# PARAMETRIK_crosover.net
KiCad netlist of a schematic drawn in EAGLE
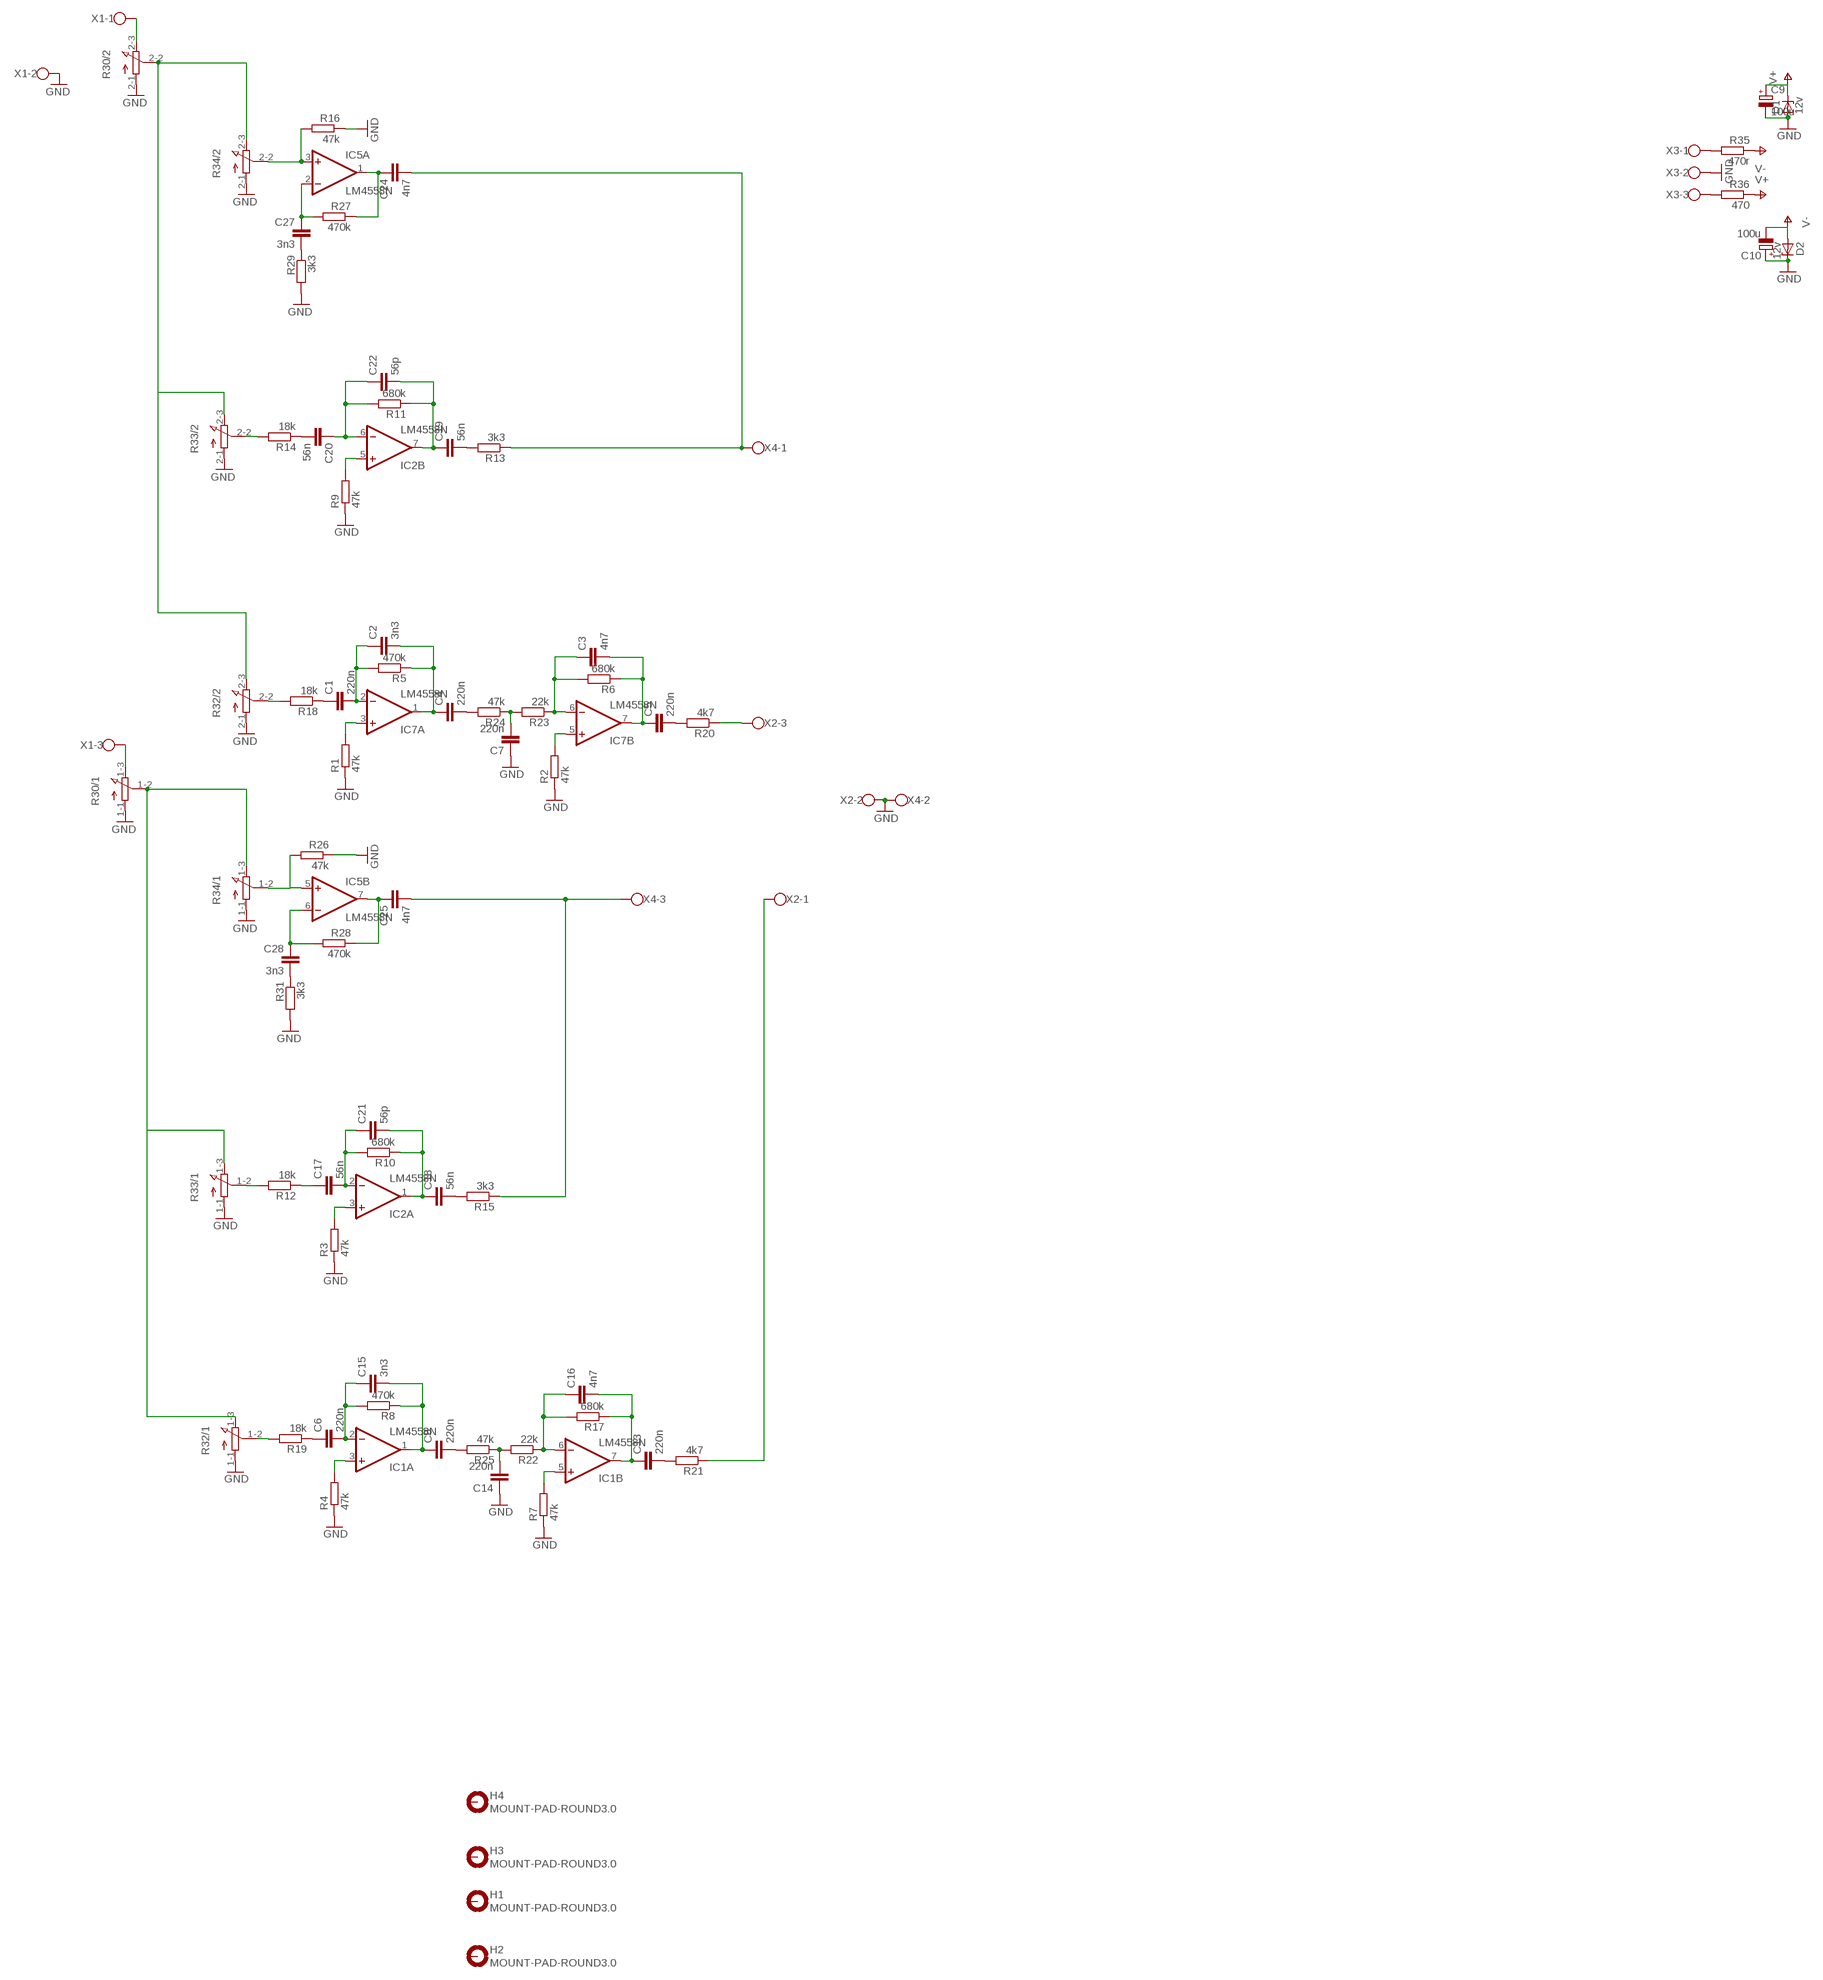
[diagram p0: schematic, sheet 1]

(export (version "E")
  (design (tool "Eeschema 10.0.6"))
  (components
    (comp (ref "C1")
      (value "220n")
      (footprint "eagle-import:C075-032X103")
      (libsource (lib "eagle-import") (part "C-EU075-032X103"))
    )
    (comp (ref "C2")
      (value "3n3")
      (footprint "eagle-import:C025-025X050")
      (libsource (lib "eagle-import") (part "C-EU025-025X050"))
    )
    (comp (ref "C3")
      (value "4n7")
      (footprint "eagle-import:C025-025X050")
      (libsource (lib "eagle-import") (part "C-EU025-025X050"))
    )
    (comp (ref "C4")
      (value "220n")
      (footprint "eagle-import:C075-032X103")
      (libsource (lib "eagle-import") (part "C-EU075-032X103"))
    )
    (comp (ref "C5")
      (value "220n")
      (footprint "eagle-import:C075-032X103")
      (libsource (lib "eagle-import") (part "C-EU075-032X103"))
    )
    (comp (ref "C6")
      (value "220n")
      (footprint "eagle-import:C075-032X103")
      (libsource (lib "eagle-import") (part "C-EU075-032X103"))
    )
    (comp (ref "C7")
      (value "220n")
      (footprint "eagle-import:C075-032X103")
      (libsource (lib "eagle-import") (part "C-EU075-032X103"))
    )
    (comp (ref "C8")
      (value "220n")
      (footprint "eagle-import:C075-032X103")
      (libsource (lib "eagle-import") (part "C-EU075-032X103"))
    )
    (comp (ref "C9")
      (value "100u")
      (footprint "eagle-import:E2,5-6")
      (libsource (lib "eagle-import") (part "CPOL-EUE2.5-6"))
    )
    (comp (ref "C10")
      (value "100u")
      (footprint "eagle-import:E2,5-6")
      (libsource (lib "eagle-import") (part "CPOL-EUE2.5-6"))
    )
    (comp (ref "C13")
      (value "220n")
      (footprint "eagle-import:C075-032X103")
      (libsource (lib "eagle-import") (part "C-EU075-032X103"))
    )
    (comp (ref "C14")
      (value "220n")
      (footprint "eagle-import:C075-032X103")
      (libsource (lib "eagle-import") (part "C-EU075-032X103"))
    )
    (comp (ref "C15")
      (value "3n3")
      (footprint "eagle-import:C025-025X050")
      (libsource (lib "eagle-import") (part "C-EU025-025X050"))
    )
    (comp (ref "C16")
      (value "4n7")
      (footprint "eagle-import:C025-025X050")
      (libsource (lib "eagle-import") (part "C-EU025-025X050"))
    )
    (comp (ref "C17")
      (value "56n")
      (footprint "eagle-import:C075-032X103")
      (libsource (lib "eagle-import") (part "C-EU075-032X103"))
    )
    (comp (ref "C18")
      (value "56n")
      (footprint "eagle-import:C075-032X103")
      (libsource (lib "eagle-import") (part "C-EU075-032X103"))
    )
    (comp (ref "C19")
      (value "56n")
      (footprint "eagle-import:C075-032X103")
      (libsource (lib "eagle-import") (part "C-EU075-032X103"))
    )
    (comp (ref "C20")
      (value "56n")
      (footprint "eagle-import:C075-032X103")
      (libsource (lib "eagle-import") (part "C-EU075-032X103"))
    )
    (comp (ref "C21")
      (value "56p")
      (footprint "eagle-import:C025-025X050")
      (libsource (lib "eagle-import") (part "C-EU025-025X050"))
    )
    (comp (ref "C22")
      (value "56p")
      (footprint "eagle-import:C025-025X050")
      (libsource (lib "eagle-import") (part "C-EU025-025X050"))
    )
    (comp (ref "C24")
      (value "4n7")
      (footprint "eagle-import:C075-032X103")
      (libsource (lib "eagle-import") (part "C-EU075-032X103"))
    )
    (comp (ref "C25")
      (value "4n7")
      (footprint "eagle-import:C075-032X103")
      (libsource (lib "eagle-import") (part "C-EU075-032X103"))
    )
    (comp (ref "C27")
      (value "3n3")
      (footprint "eagle-import:C025-025X050")
      (libsource (lib "eagle-import") (part "C-EU025-025X050"))
    )
    (comp (ref "C28")
      (value "3n3")
      (footprint "eagle-import:C025-025X050")
      (libsource (lib "eagle-import") (part "C-EU025-025X050"))
    )
    (comp (ref "D1")
      (value "12v")
      (footprint "eagle-import:DO35Z10")
      (libsource (lib "eagle-import") (part "1N821"))
    )
    (comp (ref "D2")
      (value "12v")
      (footprint "eagle-import:DO35Z10")
      (libsource (lib "eagle-import") (part "1N821"))
    )
    (comp (ref "H1")
      (value "MOUNT-PAD-ROUND3.0")
      (footprint "eagle-import:3,0-PAD")
      (libsource (lib "eagle-import") (part "MOUNT-PAD-ROUND3.0"))
    )
    (comp (ref "H2")
      (value "MOUNT-PAD-ROUND3.0")
      (footprint "eagle-import:3,0-PAD")
      (libsource (lib "eagle-import") (part "MOUNT-PAD-ROUND3.0"))
    )
    (comp (ref "H3")
      (value "MOUNT-PAD-ROUND3.0")
      (footprint "eagle-import:3,0-PAD")
      (libsource (lib "eagle-import") (part "MOUNT-PAD-ROUND3.0"))
    )
    (comp (ref "H4")
      (value "MOUNT-PAD-ROUND3.0")
      (footprint "eagle-import:3,0-PAD")
      (libsource (lib "eagle-import") (part "MOUNT-PAD-ROUND3.0"))
    )
    (comp (ref "IC1")
      (value "LM4558N")
      (footprint "eagle-import:DIL08")
      (libsource (lib "eagle-import") (part "4558NLM"))
    )
    (comp (ref "IC2")
      (value "LM4558N")
      (footprint "eagle-import:DIL08")
      (libsource (lib "eagle-import") (part "4558NLM"))
    )
    (comp (ref "IC5")
      (value "LM4558N")
      (footprint "eagle-import:DIL08")
      (libsource (lib "eagle-import") (part "4558NLM"))
    )
    (comp (ref "IC7")
      (value "LM4558N")
      (footprint "eagle-import:DIL08")
      (libsource (lib "eagle-import") (part "4558NLM"))
    )
    (comp (ref "R1")
      (value "47k")
      (footprint "eagle-import:0207_10")
      (libsource (lib "eagle-import") (part "R-EU_0207/10"))
    )
    (comp (ref "R2")
      (value "47k")
      (footprint "eagle-import:0207_10")
      (libsource (lib "eagle-import") (part "R-EU_0207/10"))
    )
    (comp (ref "R3")
      (value "47k")
      (footprint "eagle-import:0207_10")
      (libsource (lib "eagle-import") (part "R-EU_0207/10"))
    )
    (comp (ref "R4")
      (value "47k")
      (footprint "eagle-import:0207_10")
      (libsource (lib "eagle-import") (part "R-EU_0207/10"))
    )
    (comp (ref "R5")
      (value "470k")
      (footprint "eagle-import:0207_10")
      (libsource (lib "eagle-import") (part "R-EU_0207/10"))
    )
    (comp (ref "R6")
      (value "680k")
      (footprint "eagle-import:0207_10")
      (libsource (lib "eagle-import") (part "R-EU_0207/10"))
    )
    (comp (ref "R7")
      (value "47k")
      (footprint "eagle-import:0207_10")
      (libsource (lib "eagle-import") (part "R-EU_0207/10"))
    )
    (comp (ref "R8")
      (value "470k")
      (footprint "eagle-import:0207_10")
      (libsource (lib "eagle-import") (part "R-EU_0207/10"))
    )
    (comp (ref "R9")
      (value "47k")
      (footprint "eagle-import:0207_10")
      (libsource (lib "eagle-import") (part "R-EU_0207/10"))
    )
    (comp (ref "R10")
      (value "680k")
      (footprint "eagle-import:0207_10")
      (libsource (lib "eagle-import") (part "R-EU_0207/10"))
    )
    (comp (ref "R11")
      (value "680k")
      (footprint "eagle-import:0207_10")
      (libsource (lib "eagle-import") (part "R-EU_0207/10"))
    )
    (comp (ref "R12")
      (value "18k")
      (footprint "eagle-import:0207_10")
      (libsource (lib "eagle-import") (part "R-EU_0207/10"))
    )
    (comp (ref "R13")
      (value "3k3")
      (footprint "eagle-import:0207_10")
      (libsource (lib "eagle-import") (part "R-EU_0207/10"))
    )
    (comp (ref "R14")
      (value "18k")
      (footprint "eagle-import:0207_10")
      (libsource (lib "eagle-import") (part "R-EU_0207/10"))
    )
    (comp (ref "R15")
      (value "3k3")
      (footprint "eagle-import:0207_10")
      (libsource (lib "eagle-import") (part "R-EU_0207/10"))
    )
    (comp (ref "R16")
      (value "47k")
      (footprint "eagle-import:0207_10")
      (libsource (lib "eagle-import") (part "R-EU_0207/10"))
    )
    (comp (ref "R17")
      (value "680k")
      (footprint "eagle-import:0207_10")
      (libsource (lib "eagle-import") (part "R-EU_0207/10"))
    )
    (comp (ref "R18")
      (value "18k")
      (footprint "eagle-import:0207_10")
      (libsource (lib "eagle-import") (part "R-EU_0207/10"))
    )
    (comp (ref "R19")
      (value "18k")
      (footprint "eagle-import:0207_10")
      (libsource (lib "eagle-import") (part "R-EU_0207/10"))
    )
    (comp (ref "R20")
      (value "4k7")
      (footprint "eagle-import:0207_10")
      (libsource (lib "eagle-import") (part "R-EU_0207/10"))
    )
    (comp (ref "R21")
      (value "4k7")
      (footprint "eagle-import:0207_10")
      (libsource (lib "eagle-import") (part "R-EU_0207/10"))
    )
    (comp (ref "R22")
      (value "22k")
      (footprint "eagle-import:0207_10")
      (libsource (lib "eagle-import") (part "R-EU_0207/10"))
    )
    (comp (ref "R23")
      (value "22k")
      (footprint "eagle-import:0207_10")
      (libsource (lib "eagle-import") (part "R-EU_0207/10"))
    )
    (comp (ref "R24")
      (value "47k")
      (footprint "eagle-import:0207_10")
      (libsource (lib "eagle-import") (part "R-EU_0207/10"))
    )
    (comp (ref "R25")
      (value "47k")
      (footprint "eagle-import:0207_10")
      (libsource (lib "eagle-import") (part "R-EU_0207/10"))
    )
    (comp (ref "R26")
      (value "47k")
      (footprint "eagle-import:0207_10")
      (libsource (lib "eagle-import") (part "R-EU_0207/10"))
    )
    (comp (ref "R27")
      (value "470k")
      (footprint "eagle-import:0207_10")
      (libsource (lib "eagle-import") (part "R-EU_0207/10"))
    )
    (comp (ref "R28")
      (value "470k")
      (footprint "eagle-import:0207_10")
      (libsource (lib "eagle-import") (part "R-EU_0207/10"))
    )
    (comp (ref "R29")
      (value "3k3")
      (footprint "eagle-import:0207_10")
      (libsource (lib "eagle-import") (part "R-EU_0207/10"))
    )
    (comp (ref "R30")
      (value "3RP/1610G")
      (footprint "eagle-import:3RP_1610G")
      (libsource (lib "eagle-import") (part "3RP/1610G"))
    )
    (comp (ref "R31")
      (value "3k3")
      (footprint "eagle-import:0207_10")
      (libsource (lib "eagle-import") (part "R-EU_0207/10"))
    )
    (comp (ref "R32")
      (value "3RP/1610G")
      (footprint "eagle-import:3RP_1610G")
      (libsource (lib "eagle-import") (part "3RP/1610G"))
    )
    (comp (ref "R33")
      (value "3RP/1610G")
      (footprint "eagle-import:3RP_1610G")
      (libsource (lib "eagle-import") (part "3RP/1610G"))
    )
    (comp (ref "R34")
      (value "3RP/1610G")
      (footprint "eagle-import:3RP_1610G")
      (libsource (lib "eagle-import") (part "3RP/1610G"))
    )
    (comp (ref "R35")
      (value "470r")
      (footprint "eagle-import:0207_10")
      (libsource (lib "eagle-import") (part "R-EU_0207/10"))
    )
    (comp (ref "R36")
      (value "470")
      (footprint "eagle-import:0207_10")
      (libsource (lib "eagle-import") (part "R-EU_0207/10"))
    )
    (comp (ref "X1")
      (value "W237-103")
      (footprint "eagle-import:W237-103")
      (fields (field (name "MPN") "237-103"))
      (libsource (lib "eagle-import") (part "W237-103"))
    )
    (comp (ref "X2")
      (value "W237-103")
      (footprint "eagle-import:W237-103")
      (fields (field (name "MPN") "237-103"))
      (libsource (lib "eagle-import") (part "W237-103"))
    )
    (comp (ref "X3")
      (value "W237-103")
      (footprint "eagle-import:W237-103")
      (fields (field (name "MPN") "237-103"))
      (libsource (lib "eagle-import") (part "W237-103"))
    )
    (comp (ref "X4")
      (value "W237-103")
      (footprint "eagle-import:W237-103")
      (fields (field (name "MPN") "237-103"))
      (libsource (lib "eagle-import") (part "W237-103"))
    )
  )
  (nets
    (net (code "1") (name "GND") (class "Default")
      (node (ref "C10") (pin "+") (pinfunction "+_+") (pintype "passive"))
      (node (ref "C14") (pin "1") (pinfunction "1_1") (pintype "passive"))
      (node (ref "C7") (pin "1") (pinfunction "1_1") (pintype "passive"))
      (node (ref "C9") (pin "-") (pinfunction "-_-") (pintype "passive"))
      (node (ref "D1") (pin "A") (pinfunction "A_A") (pintype "passive"))
      (node (ref "D2") (pin "C") (pinfunction "C_C") (pintype "passive"))
      (node (ref "R1") (pin "1") (pinfunction "1_1") (pintype "passive"))
      (node (ref "R16") (pin "1") (pinfunction "1_1") (pintype "passive"))
      (node (ref "R2") (pin "1") (pinfunction "1_1") (pintype "passive"))
      (node (ref "R26") (pin "1") (pinfunction "1_1") (pintype "passive"))
      (node (ref "R29") (pin "2") (pinfunction "2_2") (pintype "passive"))
      (node (ref "R3") (pin "1") (pinfunction "1_1") (pintype "passive"))
      (node (ref "R30") (pin "1-1") (pinfunction "A_1-1") (pintype "passive"))
      (node (ref "R30") (pin "2-1") (pinfunction "A_2-1") (pintype "passive"))
      (node (ref "R31") (pin "2") (pinfunction "2_2") (pintype "passive"))
      (node (ref "R32") (pin "1-1") (pinfunction "A_1-1") (pintype "passive"))
      (node (ref "R32") (pin "2-1") (pinfunction "A_2-1") (pintype "passive"))
      (node (ref "R33") (pin "1-1") (pinfunction "A_1-1") (pintype "passive"))
      (node (ref "R33") (pin "2-1") (pinfunction "A_2-1") (pintype "passive"))
      (node (ref "R34") (pin "1-1") (pinfunction "A_1-1") (pintype "passive"))
      (node (ref "R34") (pin "2-1") (pinfunction "A_2-1") (pintype "passive"))
      (node (ref "R4") (pin "1") (pinfunction "1_1") (pintype "passive"))
      (node (ref "R7") (pin "1") (pinfunction "1_1") (pintype "passive"))
      (node (ref "R9") (pin "1") (pinfunction "1_1") (pintype "passive"))
      (node (ref "X1") (pin "2") (pinfunction "KL_2") (pintype "passive"))
      (node (ref "X2") (pin "2") (pinfunction "KL_2") (pintype "passive"))
      (node (ref "X3") (pin "2") (pinfunction "KL_2") (pintype "passive"))
      (node (ref "X4") (pin "2") (pinfunction "KL_2") (pintype "passive"))
    )
    (net (code "2") (name "Net-(C1-Pad1)") (class "Default")
      (node (ref "C1") (pin "1") (pinfunction "1_1") (pintype "passive"))
      (node (ref "R18") (pin "1") (pinfunction "1_1") (pintype "passive"))
    )
    (net (code "3") (name "Net-(C4-Pad2)") (class "Default")
      (node (ref "C4") (pin "2") (pinfunction "2_2") (pintype "passive"))
      (node (ref "R24") (pin "2") (pinfunction "2_2") (pintype "passive"))
    )
    (net (code "4") (name "Net-(C5-Pad2)") (class "Default")
      (node (ref "C5") (pin "2") (pinfunction "2_2") (pintype "passive"))
      (node (ref "R20") (pin "2") (pinfunction "2_2") (pintype "passive"))
    )
    (net (code "5") (name "Net-(C6-Pad1)") (class "Default")
      (node (ref "C6") (pin "1") (pinfunction "1_1") (pintype "passive"))
      (node (ref "R19") (pin "1") (pinfunction "1_1") (pintype "passive"))
    )
    (net (code "6") (name "Net-(C7-Pad2)") (class "Default")
      (node (ref "C7") (pin "2") (pinfunction "2_2") (pintype "passive"))
      (node (ref "R23") (pin "2") (pinfunction "2_2") (pintype "passive"))
      (node (ref "R24") (pin "1") (pinfunction "1_1") (pintype "passive"))
    )
    (net (code "7") (name "Net-(C8-Pad2)") (class "Default")
      (node (ref "C8") (pin "2") (pinfunction "2_2") (pintype "passive"))
      (node (ref "R25") (pin "2") (pinfunction "2_2") (pintype "passive"))
    )
    (net (code "8") (name "Net-(C13-Pad2)") (class "Default")
      (node (ref "C13") (pin "2") (pinfunction "2_2") (pintype "passive"))
      (node (ref "R21") (pin "2") (pinfunction "2_2") (pintype "passive"))
    )
    (net (code "9") (name "Net-(C14-Pad2)") (class "Default")
      (node (ref "C14") (pin "2") (pinfunction "2_2") (pintype "passive"))
      (node (ref "R22") (pin "2") (pinfunction "2_2") (pintype "passive"))
      (node (ref "R25") (pin "1") (pinfunction "1_1") (pintype "passive"))
    )
    (net (code "10") (name "Net-(C17-Pad1)") (class "Default")
      (node (ref "C17") (pin "1") (pinfunction "1_1") (pintype "passive"))
      (node (ref "R12") (pin "1") (pinfunction "1_1") (pintype "passive"))
    )
    (net (code "11") (name "Net-(C18-Pad2)") (class "Default")
      (node (ref "C18") (pin "2") (pinfunction "2_2") (pintype "passive"))
      (node (ref "R15") (pin "2") (pinfunction "2_2") (pintype "passive"))
    )
    (net (code "12") (name "Net-(C19-Pad2)") (class "Default")
      (node (ref "C19") (pin "2") (pinfunction "2_2") (pintype "passive"))
      (node (ref "R13") (pin "2") (pinfunction "2_2") (pintype "passive"))
    )
    (net (code "13") (name "Net-(C20-Pad2)") (class "Default")
      (node (ref "C20") (pin "2") (pinfunction "2_2") (pintype "passive"))
      (node (ref "R14") (pin "1") (pinfunction "1_1") (pintype "passive"))
    )
    (net (code "14") (name "Net-(C27-Pad2)") (class "Default")
      (node (ref "C27") (pin "2") (pinfunction "2_2") (pintype "passive"))
      (node (ref "R29") (pin "1") (pinfunction "1_1") (pintype "passive"))
    )
    (net (code "15") (name "Net-(C28-Pad2)") (class "Default")
      (node (ref "C28") (pin "2") (pinfunction "2_2") (pintype "passive"))
      (node (ref "R31") (pin "1") (pinfunction "1_1") (pintype "passive"))
    )
    (net (code "16") (name "Net-(IC1A-+IN)") (class "Default")
      (node (ref "IC1") (pin "3") (pinfunction "+IN_3") (pintype "input"))
      (node (ref "R4") (pin "2") (pinfunction "2_2") (pintype "passive"))
    )
    (net (code "17") (name "Net-(IC1A--IN)") (class "Default")
      (node (ref "C15") (pin "1") (pinfunction "1_1") (pintype "passive"))
      (node (ref "C6") (pin "2") (pinfunction "2_2") (pintype "passive"))
      (node (ref "IC1") (pin "2") (pinfunction "-IN_2") (pintype "input"))
      (node (ref "R8") (pin "2") (pinfunction "2_2") (pintype "passive"))
    )
    (net (code "18") (name "Net-(IC1A-OUT)") (class "Default")
      (node (ref "C15") (pin "2") (pinfunction "2_2") (pintype "passive"))
      (node (ref "C8") (pin "1") (pinfunction "1_1") (pintype "passive"))
      (node (ref "IC1") (pin "1") (pinfunction "OUT_1") (pintype "output"))
      (node (ref "R8") (pin "1") (pinfunction "1_1") (pintype "passive"))
    )
    (net (code "19") (name "Net-(IC1B-+IN)") (class "Default")
      (node (ref "IC1") (pin "5") (pinfunction "+IN_5") (pintype "input"))
      (node (ref "R7") (pin "2") (pinfunction "2_2") (pintype "passive"))
    )
    (net (code "20") (name "Net-(IC1B--IN)") (class "Default")
      (node (ref "C16") (pin "1") (pinfunction "1_1") (pintype "passive"))
      (node (ref "IC1") (pin "6") (pinfunction "-IN_6") (pintype "input"))
      (node (ref "R17") (pin "2") (pinfunction "2_2") (pintype "passive"))
      (node (ref "R22") (pin "1") (pinfunction "1_1") (pintype "passive"))
    )
    (net (code "21") (name "Net-(IC1B-OUT)") (class "Default")
      (node (ref "C13") (pin "1") (pinfunction "1_1") (pintype "passive"))
      (node (ref "C16") (pin "2") (pinfunction "2_2") (pintype "passive"))
      (node (ref "IC1") (pin "7") (pinfunction "OUT_7") (pintype "output"))
      (node (ref "R17") (pin "1") (pinfunction "1_1") (pintype "passive"))
    )
    (net (code "22") (name "Net-(IC2A-+IN)") (class "Default")
      (node (ref "IC2") (pin "3") (pinfunction "+IN_3") (pintype "input"))
      (node (ref "R3") (pin "2") (pinfunction "2_2") (pintype "passive"))
    )
    (net (code "23") (name "Net-(IC2A--IN)") (class "Default")
      (node (ref "C17") (pin "2") (pinfunction "2_2") (pintype "passive"))
      (node (ref "C21") (pin "1") (pinfunction "1_1") (pintype "passive"))
      (node (ref "IC2") (pin "2") (pinfunction "-IN_2") (pintype "input"))
      (node (ref "R10") (pin "2") (pinfunction "2_2") (pintype "passive"))
    )
    (net (code "24") (name "Net-(IC2A-OUT)") (class "Default")
      (node (ref "C18") (pin "1") (pinfunction "1_1") (pintype "passive"))
      (node (ref "C21") (pin "2") (pinfunction "2_2") (pintype "passive"))
      (node (ref "IC2") (pin "1") (pinfunction "OUT_1") (pintype "output"))
      (node (ref "R10") (pin "1") (pinfunction "1_1") (pintype "passive"))
    )
    (net (code "25") (name "Net-(IC2B-+IN)") (class "Default")
      (node (ref "IC2") (pin "5") (pinfunction "+IN_5") (pintype "input"))
      (node (ref "R9") (pin "2") (pinfunction "2_2") (pintype "passive"))
    )
    (net (code "26") (name "Net-(IC2B--IN)") (class "Default")
      (node (ref "C20") (pin "1") (pinfunction "1_1") (pintype "passive"))
      (node (ref "C22") (pin "1") (pinfunction "1_1") (pintype "passive"))
      (node (ref "IC2") (pin "6") (pinfunction "-IN_6") (pintype "input"))
      (node (ref "R11") (pin "2") (pinfunction "2_2") (pintype "passive"))
    )
    (net (code "27") (name "Net-(IC2B-OUT)") (class "Default")
      (node (ref "C19") (pin "1") (pinfunction "1_1") (pintype "passive"))
      (node (ref "C22") (pin "2") (pinfunction "2_2") (pintype "passive"))
      (node (ref "IC2") (pin "7") (pinfunction "OUT_7") (pintype "output"))
      (node (ref "R11") (pin "1") (pinfunction "1_1") (pintype "passive"))
    )
    (net (code "28") (name "Net-(IC5A-+IN)") (class "Default")
      (node (ref "IC5") (pin "3") (pinfunction "+IN_3") (pintype "input"))
      (node (ref "R16") (pin "2") (pinfunction "2_2") (pintype "passive"))
      (node (ref "R34") (pin "2-2") (pinfunction "S_2-2") (pintype "passive"))
    )
    (net (code "29") (name "Net-(IC5A--IN)") (class "Default")
      (node (ref "C27") (pin "1") (pinfunction "1_1") (pintype "passive"))
      (node (ref "IC5") (pin "2") (pinfunction "-IN_2") (pintype "input"))
      (node (ref "R27") (pin "2") (pinfunction "2_2") (pintype "passive"))
    )
    (net (code "30") (name "Net-(IC5A-OUT)") (class "Default")
      (node (ref "C24") (pin "1") (pinfunction "1_1") (pintype "passive"))
      (node (ref "IC5") (pin "1") (pinfunction "OUT_1") (pintype "output"))
      (node (ref "R27") (pin "1") (pinfunction "1_1") (pintype "passive"))
    )
    (net (code "31") (name "Net-(IC5B-+IN)") (class "Default")
      (node (ref "IC5") (pin "5") (pinfunction "+IN_5") (pintype "input"))
      (node (ref "R26") (pin "2") (pinfunction "2_2") (pintype "passive"))
      (node (ref "R34") (pin "1-2") (pinfunction "S_1-2") (pintype "passive"))
    )
    (net (code "32") (name "Net-(IC5B--IN)") (class "Default")
      (node (ref "C28") (pin "1") (pinfunction "1_1") (pintype "passive"))
      (node (ref "IC5") (pin "6") (pinfunction "-IN_6") (pintype "input"))
      (node (ref "R28") (pin "2") (pinfunction "2_2") (pintype "passive"))
    )
    (net (code "33") (name "Net-(IC5B-OUT)") (class "Default")
      (node (ref "C25") (pin "1") (pinfunction "1_1") (pintype "passive"))
      (node (ref "IC5") (pin "7") (pinfunction "OUT_7") (pintype "output"))
      (node (ref "R28") (pin "1") (pinfunction "1_1") (pintype "passive"))
    )
    (net (code "34") (name "Net-(IC7A-+IN)") (class "Default")
      (node (ref "IC7") (pin "3") (pinfunction "+IN_3") (pintype "input"))
      (node (ref "R1") (pin "2") (pinfunction "2_2") (pintype "passive"))
    )
    (net (code "35") (name "Net-(IC7A--IN)") (class "Default")
      (node (ref "C1") (pin "2") (pinfunction "2_2") (pintype "passive"))
      (node (ref "C2") (pin "1") (pinfunction "1_1") (pintype "passive"))
      (node (ref "IC7") (pin "2") (pinfunction "-IN_2") (pintype "input"))
      (node (ref "R5") (pin "2") (pinfunction "2_2") (pintype "passive"))
    )
    (net (code "36") (name "Net-(IC7A-OUT)") (class "Default")
      (node (ref "C2") (pin "2") (pinfunction "2_2") (pintype "passive"))
      (node (ref "C4") (pin "1") (pinfunction "1_1") (pintype "passive"))
      (node (ref "IC7") (pin "1") (pinfunction "OUT_1") (pintype "output"))
      (node (ref "R5") (pin "1") (pinfunction "1_1") (pintype "passive"))
    )
    (net (code "37") (name "Net-(IC7B-+IN)") (class "Default")
      (node (ref "IC7") (pin "5") (pinfunction "+IN_5") (pintype "input"))
      (node (ref "R2") (pin "2") (pinfunction "2_2") (pintype "passive"))
    )
    (net (code "38") (name "Net-(IC7B--IN)") (class "Default")
      (node (ref "C3") (pin "1") (pinfunction "1_1") (pintype "passive"))
      (node (ref "IC7") (pin "6") (pinfunction "-IN_6") (pintype "input"))
      (node (ref "R23") (pin "1") (pinfunction "1_1") (pintype "passive"))
      (node (ref "R6") (pin "2") (pinfunction "2_2") (pintype "passive"))
    )
    (net (code "39") (name "Net-(IC7B-OUT)") (class "Default")
      (node (ref "C3") (pin "2") (pinfunction "2_2") (pintype "passive"))
      (node (ref "C5") (pin "1") (pinfunction "1_1") (pintype "passive"))
      (node (ref "IC7") (pin "7") (pinfunction "OUT_7") (pintype "output"))
      (node (ref "R6") (pin "1") (pinfunction "1_1") (pintype "passive"))
    )
    (net (code "40") (name "Net-(R30A-E)") (class "Default")
      (node (ref "R30") (pin "1-3") (pinfunction "E_1-3") (pintype "passive"))
      (node (ref "X1") (pin "3") (pinfunction "KL_3") (pintype "passive"))
    )
    (net (code "41") (name "Net-(R30A-S)") (class "Default")
      (node (ref "R30") (pin "1-2") (pinfunction "S_1-2") (pintype "passive"))
      (node (ref "R32") (pin "1-3") (pinfunction "E_1-3") (pintype "passive"))
      (node (ref "R33") (pin "1-3") (pinfunction "E_1-3") (pintype "passive"))
      (node (ref "R34") (pin "1-3") (pinfunction "E_1-3") (pintype "passive"))
    )
    (net (code "42") (name "Net-(R30B-E)") (class "Default")
      (node (ref "R30") (pin "2-3") (pinfunction "E_2-3") (pintype "passive"))
      (node (ref "X1") (pin "1") (pinfunction "KL_1") (pintype "passive"))
    )
    (net (code "43") (name "Net-(R30B-S)") (class "Default")
      (node (ref "R30") (pin "2-2") (pinfunction "S_2-2") (pintype "passive"))
      (node (ref "R32") (pin "2-3") (pinfunction "E_2-3") (pintype "passive"))
      (node (ref "R33") (pin "2-3") (pinfunction "E_2-3") (pintype "passive"))
      (node (ref "R34") (pin "2-3") (pinfunction "E_2-3") (pintype "passive"))
    )
    (net (code "44") (name "Net-(R32A-S)") (class "Default")
      (node (ref "R19") (pin "2") (pinfunction "2_2") (pintype "passive"))
      (node (ref "R32") (pin "1-2") (pinfunction "S_1-2") (pintype "passive"))
    )
    (net (code "45") (name "Net-(R32B-S)") (class "Default")
      (node (ref "R18") (pin "2") (pinfunction "2_2") (pintype "passive"))
      (node (ref "R32") (pin "2-2") (pinfunction "S_2-2") (pintype "passive"))
    )
    (net (code "46") (name "Net-(R33A-S)") (class "Default")
      (node (ref "R12") (pin "2") (pinfunction "2_2") (pintype "passive"))
      (node (ref "R33") (pin "1-2") (pinfunction "S_1-2") (pintype "passive"))
    )
    (net (code "47") (name "Net-(R33B-S)") (class "Default")
      (node (ref "R14") (pin "2") (pinfunction "2_2") (pintype "passive"))
      (node (ref "R33") (pin "2-2") (pinfunction "S_2-2") (pintype "passive"))
    )
    (net (code "48") (name "Net-(X2A-KL)") (class "Default")
      (node (ref "R21") (pin "1") (pinfunction "1_1") (pintype "passive"))
      (node (ref "X2") (pin "1") (pinfunction "KL_1") (pintype "passive"))
    )
    (net (code "49") (name "Net-(X2C-KL)") (class "Default")
      (node (ref "R20") (pin "1") (pinfunction "1_1") (pintype "passive"))
      (node (ref "X2") (pin "3") (pinfunction "KL_3") (pintype "passive"))
    )
    (net (code "50") (name "Net-(X3A-KL)") (class "Default")
      (node (ref "R35") (pin "2") (pinfunction "2_2") (pintype "passive"))
      (node (ref "X3") (pin "1") (pinfunction "KL_1") (pintype "passive"))
    )
    (net (code "51") (name "Net-(X3C-KL)") (class "Default")
      (node (ref "R36") (pin "2") (pinfunction "2_2") (pintype "passive"))
      (node (ref "X3") (pin "3") (pinfunction "KL_3") (pintype "passive"))
    )
    (net (code "52") (name "Net-(X4A-KL)") (class "Default")
      (node (ref "C24") (pin "2") (pinfunction "2_2") (pintype "passive"))
      (node (ref "R13") (pin "1") (pinfunction "1_1") (pintype "passive"))
      (node (ref "X4") (pin "1") (pinfunction "KL_1") (pintype "passive"))
    )
    (net (code "53") (name "Net-(X4C-KL)") (class "Default")
      (node (ref "C25") (pin "2") (pinfunction "2_2") (pintype "passive"))
      (node (ref "R15") (pin "1") (pinfunction "1_1") (pintype "passive"))
      (node (ref "X4") (pin "3") (pinfunction "KL_3") (pintype "passive"))
    )
    (net (code "54") (name "V+") (class "Default")
      (node (ref "C9") (pin "+") (pinfunction "+_+") (pintype "passive"))
      (node (ref "D1") (pin "C") (pinfunction "C_C") (pintype "passive"))
      (node (ref "R36") (pin "1") (pinfunction "1_1") (pintype "passive"))
    )
    (net (code "55") (name "V-") (class "Default")
      (node (ref "C10") (pin "-") (pinfunction "-_-") (pintype "passive"))
      (node (ref "D2") (pin "A") (pinfunction "A_A") (pintype "passive"))
      (node (ref "R35") (pin "1") (pinfunction "1_1") (pintype "passive"))
    )
    (net (code "56") (name "unconnected-(H1-MOUNT-PadB3,0)") (class "Default")
      (node (ref "H1") (pin "B3,0") (pinfunction "MOUNT_B3,0") (pintype "passive"))
    )
    (net (code "57") (name "unconnected-(H2-MOUNT-PadB3,0)") (class "Default")
      (node (ref "H2") (pin "B3,0") (pinfunction "MOUNT_B3,0") (pintype "passive"))
    )
    (net (code "58") (name "unconnected-(H3-MOUNT-PadB3,0)") (class "Default")
      (node (ref "H3") (pin "B3,0") (pinfunction "MOUNT_B3,0") (pintype "passive"))
    )
    (net (code "59") (name "unconnected-(H4-MOUNT-PadB3,0)") (class "Default")
      (node (ref "H4") (pin "B3,0") (pinfunction "MOUNT_B3,0") (pintype "passive"))
    )
  )
)
